# 11_sensors.net
KiCad netlist of a schematic drawn in Altium Designer
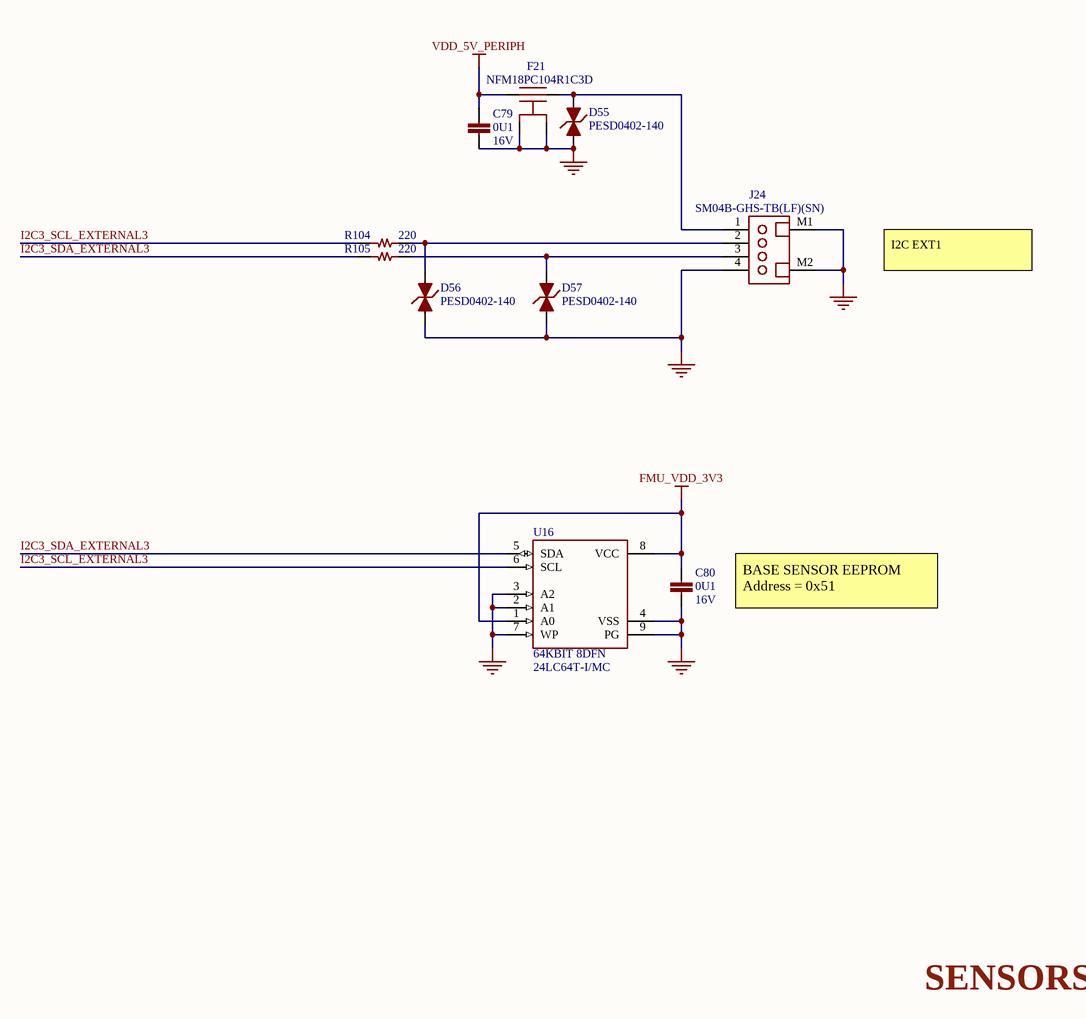
[diagram p0: 11_sensors.SchDoc]

(export (version "E")
  (design (tool "Eeschema 10.0.6"))
  (components
    (comp (ref "C79")
      (value "0U1")
      (footprint "CAPC100X50X56L25N")
      (description "CAP CER 0.1UF 10% 16V X7R 0402")
      (fields
        (field (name "TOLERANCE") "±10%")
        (field (name "MANUFACTURER") "Murata Electronics")
        (field (name "VOLTAGE - RATED") "16V")
      )
      (libsource (lib "NscDG_Integrated_Library") (part "CAP_0U1_16V_X7R_0402"))
    )
    (comp (ref "C80")
      (value "0U1")
      (footprint "CAPC100X50X56L25N")
      (description "CAP CER 0.1UF 10% 16V X7R 0402")
      (fields
        (field (name "TOLERANCE") "±10%")
        (field (name "MANUFACTURER") "Murata Electronics")
        (field (name "VOLTAGE - RATED") "16V")
      )
      (libsource (lib "NscDG_Integrated_Library") (part "CAP_0U1_16V_X7R_0402"))
    )
    (comp (ref "D55")
      (value "DIODE TVS BIDIRECTIONAL 14VWM 40VC 0402")
      (footprint "DIONC100X50X43L20N")
      (fields
        (field (name "MANUFACTURER") "Littelfuse Inc.")
        (field (name "MANUFACTURER PART NUMBER") "PESD0402-140")
      )
      (libsource (lib "NscDG_Integrated_Library") (part "DIODE_TVS_0402"))
    )
    (comp (ref "D56")
      (value "DIODE TVS BIDIRECTIONAL 14VWM 40VC 0402")
      (footprint "DIONC100X50X43L20N")
      (fields
        (field (name "MANUFACTURER") "Littelfuse Inc.")
        (field (name "MANUFACTURER PART NUMBER") "PESD0402-140")
      )
      (libsource (lib "NscDG_Integrated_Library") (part "DIODE_TVS_0402"))
    )
    (comp (ref "D57")
      (value "DIODE TVS BIDIRECTIONAL 14VWM 40VC 0402")
      (footprint "DIONC100X50X43L20N")
      (fields
        (field (name "MANUFACTURER") "Littelfuse Inc.")
        (field (name "MANUFACTURER PART NUMBER") "PESD0402-140")
      )
      (libsource (lib "NscDG_Integrated_Library") (part "DIODE_TVS_0402"))
    )
    (comp (ref "F21")
      (value "FILTER CAP FEEDTHRU 0.1UF 20% 16V 0603")
      (footprint "NFM18PC104R1C3_0603_NO_VIA")
      (fields
        (field (name "TOLERANCE") "±20%")
        (field (name "MANUFACTURER") "Murata Electronics North America")
        (field (name "MANUFACTURER PART NUMBER") "NFM18PC104R1C3D")
      )
      (libsource (lib "NscDG_Integrated_Library") (part "FILTER_0.1uF_16V_2A_NO_VIA_0603"))
    )
    (comp (ref "J24")
      (value "CONN HEADER GH SIDE 4POS 1.25MM SMT")
      (footprint "JST_SM04B-GHS-TBLFSN")
      (fields
        (field (name "MANUFACTURER") "JST Sales America Inc.")
        (field (name "MANUFACTURER PART NUMBER") "SM04B-GHS-TB(LF)(SN)")
      )
      (libsource (lib "NscDG_Integrated_Library") (part "CONN_JST_GH_4PIN_RA_SMT"))
    )
    (comp (ref "R104")
      (value "220")
      (footprint "RESC100X50X40L25")
      (description "RES SMD 220 OHM 1% 1/16W 0402")
      (fields (field (name "TOLERANCE") "±1%") (field (name "POWER") "1/16W"))
      (libsource (lib "NscDG_Integrated_Library") (part "RES_220_1%_1/16W_0402"))
    )
    (comp (ref "R105")
      (value "220")
      (footprint "RESC100X50X40L25")
      (description "RES SMD 220 OHM 1% 1/16W 0402")
      (fields (field (name "TOLERANCE") "±1%") (field (name "POWER") "1/16W"))
      (libsource (lib "NscDG_Integrated_Library") (part "RES_220_1%_1/16W_0402"))
    )
    (comp (ref "U16")
      (value "IC EEPROM 64K I2C 400KHZ 8DFN")
      (footprint "SON9P50_200X300X100L40X25T153X170N")
      (fields
        (field (name "MANUFACTURER") "Microchip Technology")
        (field (name "ID") "64KBIT 8DFN")
        (field (name "MANUFACTURER PART NUMBER") "24LC64T-I/MC")
      )
      (libsource (lib "NscDG_Integrated_Library") (part "IC_EEPROM_64K_I2C_8DFN"))
    )
  )
  (nets
    (net (code "1") (name "/I2C3_SCL_EXTERNAL3") (class "Default")
      (node (ref "R104") (pin "1") (pinfunction "1_1") (pintype "passive"))
      (node (ref "U16") (pin "6") (pinfunction "SCL_6") (pintype "input"))
    )
    (net (code "2") (name "/I2C3_SDA_EXTERNAL3") (class "Default")
      (node (ref "R105") (pin "1") (pinfunction "1_1") (pintype "passive"))
      (node (ref "U16") (pin "5") (pinfunction "SDA_5") (pintype "bidirectional"))
    )
    (net (code "3") (name "FMU_VDD_3V3") (class "Default")
      (node (ref "C80") (pin "1") (pinfunction "1_1") (pintype "passive"))
      (node (ref "U16") (pin "1") (pinfunction "A0_1") (pintype "input"))
      (node (ref "U16") (pin "8") (pinfunction "VCC_8") (pintype "power_in"))
    )
    (net (code "4") (name "GND") (class "Default")
      (node (ref "C79") (pin "2") (pinfunction "2_2") (pintype "passive"))
      (node (ref "C80") (pin "2") (pinfunction "2_2") (pintype "passive"))
      (node (ref "D55") (pin "1") (pinfunction "1_1") (pintype "passive"))
      (node (ref "D56") (pin "1") (pinfunction "1_1") (pintype "passive"))
      (node (ref "D57") (pin "1") (pinfunction "1_1") (pintype "passive"))
      (node (ref "F21") (pin "2A") (pinfunction "GND_2A") (pintype "passive"))
      (node (ref "F21") (pin "2B") (pinfunction "GND_2B") (pintype "passive"))
      (node (ref "J24") (pin "4") (pinfunction "4_4") (pintype "passive"))
      (node (ref "J24") (pin "M1") (pinfunction "M1_M1") (pintype "passive"))
      (node (ref "J24") (pin "M2") (pinfunction "M2_M2") (pintype "passive"))
      (node (ref "U16") (pin "2") (pinfunction "A1_2") (pintype "input"))
      (node (ref "U16") (pin "3") (pinfunction "A2_3") (pintype "input"))
      (node (ref "U16") (pin "4") (pinfunction "VSS_4") (pintype "passive"))
      (node (ref "U16") (pin "7") (pinfunction "WP_7") (pintype "input"))
      (node (ref "U16") (pin "9") (pinfunction "PG_9") (pintype "passive"))
    )
    (net (code "5") (name "Net-(D55-Pad2)") (class "Default")
      (node (ref "D55") (pin "2") (pinfunction "2_2") (pintype "passive"))
      (node (ref "F21") (pin "3") (pinfunction "3_3") (pintype "passive"))
      (node (ref "J24") (pin "1") (pinfunction "1_1") (pintype "passive"))
    )
    (net (code "6") (name "Net-(D56-Pad2)") (class "Default")
      (node (ref "D56") (pin "2") (pinfunction "2_2") (pintype "passive"))
      (node (ref "J24") (pin "2") (pinfunction "2_2") (pintype "passive"))
      (node (ref "R104") (pin "2") (pinfunction "2_2") (pintype "passive"))
    )
    (net (code "7") (name "Net-(D57-Pad2)") (class "Default")
      (node (ref "D57") (pin "2") (pinfunction "2_2") (pintype "passive"))
      (node (ref "J24") (pin "3") (pinfunction "3_3") (pintype "passive"))
      (node (ref "R105") (pin "2") (pinfunction "2_2") (pintype "passive"))
    )
    (net (code "8") (name "VDD_5V_PERIPH") (class "Default")
      (node (ref "C79") (pin "1") (pinfunction "1_1") (pintype "passive"))
      (node (ref "F21") (pin "1") (pinfunction "1_1") (pintype "passive"))
    )
  )
)
